# MCU.net
KiCad netlist of a schematic drawn in Altium Designer
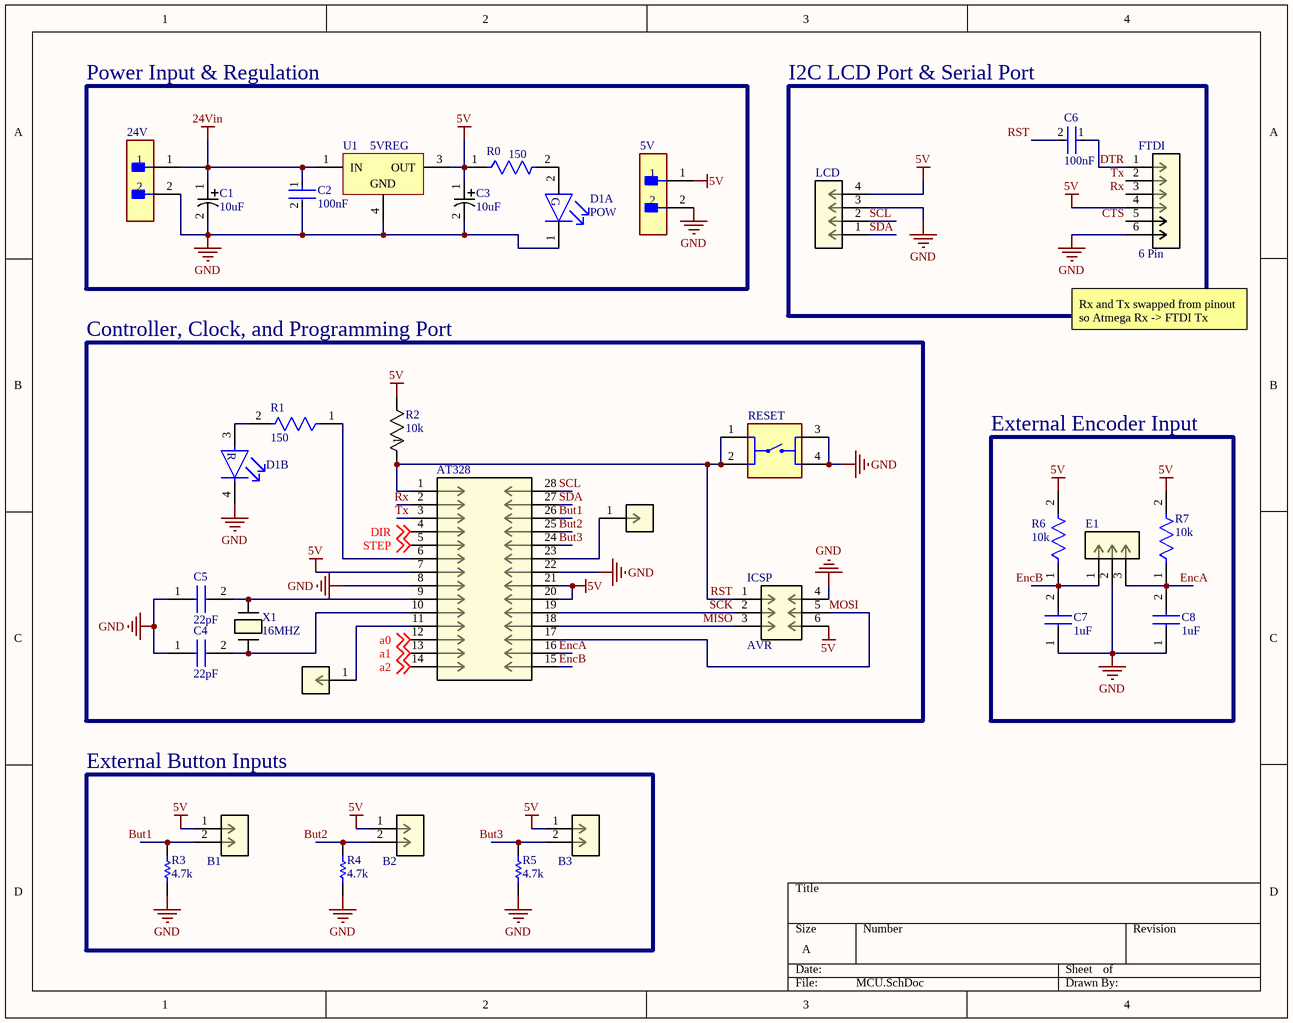
[diagram p0: MCU.SchDoc]

(export (version "E")
  (design (tool "Eeschema 10.0.6"))
  (components
    (comp (ref "5V")
      (value "~")
      (footprint "FP-TSW-102-07-L-S-MFG")
      (description "CONN HEADER VERT 2POS 2.54MM   TSW-102-07-L-S")
      (libsource (lib "Altium Content Vault") (part "3bc925449376181038e59eaffc5286c"))
    )
    (comp (ref "24V")
      (value "~")
      (footprint "FP-TSW-102-07-L-S-MFG")
      (description "CONN HEADER VERT 2POS 2.54MM   TSW-102-07-L-S")
      (libsource (lib "Altium Content Vault") (part "3bc925449376181038e59eaffc5286c"))
    )
    (comp (ref "AT328")
      (value "Atmega328")
      (footprint "PcbLib1:CONN28_1-2199298-9_TEC")
      (description "No Description Available   1-2199298-9")
      (fields
        (field (name "MANUFACTURER_PART_NUMBER") "1-2199298-9")
        (field (name "COPYRIGHT") "Copyright (C) 2022 Ultra Librarian. All rights reserved.")
      )
      (libsource (lib "Schlib1") (part "14x2_J"))
    )
    (comp (ref "B1")
      (value "Header")
      (footprint "PcbLib1:1x2StanHeader")
      (description "No Description Available")
      (fields
        (field (name "MANUFACTURER_PART_NUMBER") "5-826631-0")
        (field (name "COPYRIGHT") "Copyright (C) 2018 Accelerated Designs. All rights reserved")
      )
      (libsource (lib "Schlib1") (part "2x1_J"))
    )
    (comp (ref "B2")
      (value "Header")
      (footprint "PcbLib1:1x2StanHeader")
      (description "No Description Available")
      (fields
        (field (name "MANUFACTURER_PART_NUMBER") "5-826631-0")
        (field (name "COPYRIGHT") "Copyright (C) 2018 Accelerated Designs. All rights reserved")
      )
      (libsource (lib "Schlib1") (part "2x1_J"))
    )
    (comp (ref "B3")
      (value "Header")
      (footprint "PcbLib1:1x2StanHeader")
      (description "No Description Available")
      (fields
        (field (name "MANUFACTURER_PART_NUMBER") "5-826631-0")
        (field (name "COPYRIGHT") "Copyright (C) 2018 Accelerated Designs. All rights reserved")
      )
      (libsource (lib "Schlib1") (part "2x1_J"))
    )
    (comp (ref "C1")
      (value "10uF")
      (footprint "PcbLib1:CAP_EEE_C_PAN-M")
      (description "EEE-1VA100SR")
      (fields (field (name "COPYRIGHT") "Copyright (C) 2022 Ultra Librarian. All rights reserved."))
      (libsource (lib "Schlib1") (part "EEE-1VA100SR"))
    )
    (comp (ref "C2")
      (value "100nF")
      (footprint "FP-CL21-IPC_C")
      (description "CL21 Series 0805 100nF 50V ±10% Tolerance X7R Multilayer Ceramic Chip Capacitor CL21B104KBCNNNC")
      (fields (field (name "TOLERANCE") "10%") (field (name "VOLTAGE") "50V"))
      (libsource (lib "Altium Content Vault") (part "b4654b650e69147ec39a6b967a45e02"))
    )
    (comp (ref "C3")
      (value "10uF")
      (footprint "PcbLib1:CAP_EEE_C_PAN-M")
      (description "EEE-1VA100SR")
      (fields (field (name "COPYRIGHT") "Copyright (C) 2022 Ultra Librarian. All rights reserved."))
      (libsource (lib "Schlib1") (part "EEE-1VA100SR"))
    )
    (comp (ref "C4")
      (value "22pF")
      (footprint "PcbLib1:C0805")
      (description "Capacitor C0805C220J4GACTU")
      (fields
        (field (name "MOUSER2 PART NUMBER") "80-C0805C220J4GACTU")
        (field (name "MANUFACTURER_PART_NUMBER") "C0805C220J4GACTU")
      )
      (libsource (lib "Schlib1") (part "C0805C220J4GACTU"))
    )
    (comp (ref "C5")
      (value "22pF")
      (footprint "PcbLib1:C0805")
      (description "Capacitor C0805C220J4GACTU")
      (fields
        (field (name "MOUSER2 PART NUMBER") "80-C0805C220J4GACTU")
        (field (name "MANUFACTURER_PART_NUMBER") "C0805C220J4GACTU")
      )
      (libsource (lib "Schlib1") (part "C0805C220J4GACTU"))
    )
    (comp (ref "C6")
      (value "100nF")
      (footprint "FP-CL21-IPC_C")
      (description "CL21 Series 0805 100nF 50V ±10% Tolerance X7R Multilayer Ceramic Chip Capacitor CL21B104KBCNNNC")
      (fields (field (name "TOLERANCE") "10%") (field (name "VOLTAGE") "50V"))
      (libsource (lib "Altium Content Vault") (part "b4654b650e69147ec39a6b967a45e02"))
    )
    (comp (ref "C7")
      (value "1uF")
      (footprint "PcbLib1:CAPC2012X135N")
      (description "Capacitor CL21B105KAFNNNE")
      (fields
        (field (name "MANUFACTURER_PART_NUMBER") "CL21B105KAFNNNE")
        (field (name "MOUSER PART NUMBER") "187-CL21B105KAFNNNE")
      )
      (libsource (lib "Schlib1") (part "CL21B105KAFNNNE"))
    )
    (comp (ref "C8")
      (value "1uF")
      (footprint "PcbLib1:CAPC2012X135N")
      (description "Capacitor CL21B105KAFNNNE")
      (fields
        (field (name "MANUFACTURER_PART_NUMBER") "CL21B105KAFNNNE")
        (field (name "MOUSER PART NUMBER") "187-CL21B105KAFNNNE")
      )
      (libsource (lib "Schlib1") (part "CL21B105KAFNNNE"))
    )
    (comp (ref "D1")
      (value "POW")
      (footprint "FP-LTST-C235KGKRKT-MFG")
      (description "LED GREEN/RED CLEAR CHIP SMD LTST-C235KGKRKT")
      (libsource (lib "Altium Content Vault") (part "5532c11a9016f0da2f6b1749dd462ab"))
    )
    (comp (ref "E1")
      (value "Encoder")
      (footprint "PcbLib1:1x3StanHeader")
      (description "No Description Available")
      (fields
        (field (name "MANUFACTURER_PART_NUMBER") "5-826631-0")
        (field (name "COPYRIGHT") "Copyright (C) 2018 Accelerated Designs. All rights reserved")
      )
      (libsource (lib "Schlib1") (part "3x1_J"))
    )
    (comp (ref "FTDI")
      (value "6 Pin")
      (footprint "PcbLib1:USB FTDI 1x6")
      (description "No Description Available")
      (fields
        (field (name "MANUFACTURER_PART_NUMBER") "5-826631-0")
        (field (name "COPYRIGHT") "Copyright (C) 2018 Accelerated Designs. All rights reserved")
      )
      (libsource (lib "Schlib1") (part "FTDI USB"))
    )
    (comp (ref "ICSP")
      (value "AVR")
      (footprint "PcbLib1:2x3StanHeader")
      (description "No Description Available")
      (fields
        (field (name "MANUFACTURER_PART_NUMBER") "5-826631-0")
        (field (name "COPYRIGHT") "Copyright (C) 2018 Accelerated Designs. All rights reserved")
      )
      (libsource (lib "Schlib1") (part "2x3_J"))
    )
    (comp (ref "JB")
      (value "Header")
      (footprint "PcbLib1:1x1StanHeader")
      (description "No Description Available")
      (fields
        (field (name "MANUFACTURER_PART_NUMBER") "5-826631-0")
        (field (name "COPYRIGHT") "Copyright (C) 2018 Accelerated Designs. All rights reserved")
      )
      (libsource (lib "Schlib1") (part "1x1_J"))
    )
    (comp (ref "JC")
      (value "Header")
      (footprint "PcbLib1:1x1StanHeader")
      (description "No Description Available")
      (fields
        (field (name "MANUFACTURER_PART_NUMBER") "5-826631-0")
        (field (name "COPYRIGHT") "Copyright (C) 2018 Accelerated Designs. All rights reserved")
      )
      (libsource (lib "") (part "1x1_J_1"))
    )
    (comp (ref "LCD")
      (value "LCD")
      (footprint "PcbLib1:1x4StanHeader")
      (description "No Description Available")
      (fields
        (field (name "MANUFACTURER_PART_NUMBER") "5-826631-0")
        (field (name "COPYRIGHT") "Copyright (C) 2018 Accelerated Designs. All rights reserved")
      )
      (libsource (lib "Schlib1") (part "4x1_J"))
    )
    (comp (ref "R0")
      (value "150")
      (footprint "FP-ERJ6GE-MFG")
      (description "RES SMD 150 OHM 5% 1/8W 0805 ERJ-6GEYJ151V")
      (fields (field (name "TOLERANCE") "5%") (field (name "MANUFACTURER PART NUMBER") "ERJ-6GEYJ151V"))
      (libsource (lib "Altium Content Vault") (part "1029c3af85768c4190bb7ad29bc67b5"))
    )
    (comp (ref "R1")
      (value "150")
      (footprint "FP-ERJ6GE-MFG")
      (description "RES SMD 150 OHM 5% 1/8W 0805 ERJ-6GEYJ151V")
      (fields (field (name "TOLERANCE") "5%") (field (name "MANUFACTURER PART NUMBER") "ERJ-6GEYJ151V"))
      (libsource (lib "Altium Content Vault") (part "1029c3af85768c4190bb7ad29bc67b5"))
    )
    (comp (ref "R2")
      (value "10k")
      (footprint "PcbLib1:RES_AC0805_YAG-M")
      (description "AC0805FR-070RL")
      (fields (field (name "COPYRIGHT") "Copyright (C) 2022 Ultra Librarian. All rights reserved."))
      (libsource (lib "Schlib1") (part "AC0805FR-070RL"))
    )
    (comp (ref "R3")
      (value "4.7k")
      (footprint "RESC2013X50X30LL20T20")
      (description "CRCW08054K70JNEB")
      (fields (field (name "MANUFACTURER") "Vishay Dale"))
      (libsource (lib "Altium Content Vault") (part "RES"))
    )
    (comp (ref "R4")
      (value "4.7k")
      (footprint "RESC2013X50X30LL20T20")
      (description "CRCW08054K70JNEB")
      (fields (field (name "MANUFACTURER") "Vishay Dale"))
      (libsource (lib "Altium Content Vault") (part "RES"))
    )
    (comp (ref "R5")
      (value "4.7k")
      (footprint "RESC2013X50X30LL20T20")
      (description "CRCW08054K70JNEB")
      (fields (field (name "MANUFACTURER") "Vishay Dale"))
      (libsource (lib "Altium Content Vault") (part "RES"))
    )
    (comp (ref "R6")
      (value "10k")
      (footprint "FP-MC01W0805-IPC_C")
      (description "Resistor, 10K, 0.1W, 1%, 0805, Reel MC01W0805110K")
      (fields (field (name "TOLERANCE") "1%"))
      (libsource (lib "Altium Content Vault") (part "1029c3af85768c4190bb7ad29bc67b5"))
    )
    (comp (ref "R7")
      (value "10k")
      (footprint "FP-MC01W0805-IPC_C")
      (description "Resistor, 10K, 0.1W, 1%, 0805, Reel MC01W0805110K")
      (fields (field (name "TOLERANCE") "1%"))
      (libsource (lib "Altium Content Vault") (part "1029c3af85768c4190bb7ad29bc67b5"))
    )
    (comp (ref "RESET")
      (value "Reset")
      (footprint "SW_1825910-6-4")
      (description "Switch Tactile OFF (ON) SPST Round Button PC Pins 0.05A 24VDC 100000Cycles 1.57N Thru-Hole Loose")
      (fields (field (name "MP") "1825910-6"))
      (libsource (lib "Panther Racing") (part "1825910-6"))
    )
    (comp (ref "U1")
      (value "5VREG")
      (footprint "TO-263_M")
      (description "Positive Voltage Regulator, 3-Pin D2PAK, Tape and Reel L7805CD2T-TR")
      (libsource (lib "Altium Content Vault") (part "PM-REG-L4940-SOT3"))
    )
    (comp (ref "X1")
      (value "16MHZ")
      (footprint "XTAL_ATS-49_CTS")
      (description "ATS-49/U-16.0000MHZ")
      (fields (field (name "COPYRIGHT") "Copyright (C) 2022 Ultra Librarian. All rights reserved."))
      (libsource (lib "Schlib1") (part "ATS-49/U-16.0000MHZ"))
    )
  )
  (nets
    (net (code "1") (name "/But1") (class "Default")
      (node (ref "AT328") (pin "26") (pinfunction "26_26") (pintype "passive"))
      (node (ref "B1") (pin "2") (pinfunction "2_2") (pintype "passive"))
      (node (ref "R3") (pin "2") (pinfunction "2_2") (pintype "passive"))
    )
    (net (code "2") (name "/But2") (class "Default")
      (node (ref "AT328") (pin "25") (pinfunction "25_25") (pintype "passive"))
      (node (ref "B2") (pin "2") (pinfunction "2_2") (pintype "passive"))
      (node (ref "R4") (pin "2") (pinfunction "2_2") (pintype "passive"))
    )
    (net (code "3") (name "/But3") (class "Default")
      (node (ref "AT328") (pin "24") (pinfunction "24_24") (pintype "passive"))
      (node (ref "B3") (pin "2") (pinfunction "2_2") (pintype "passive"))
      (node (ref "R5") (pin "2") (pinfunction "2_2") (pintype "passive"))
    )
    (net (code "4") (name "/CTS") (class "Default")
      (node (ref "FTDI") (pin "5") (pinfunction "5_5") (pintype "passive"))
    )
    (net (code "5") (name "/DTR") (class "Default")
      (node (ref "C6") (pin "1") (pinfunction "1_1") (pintype "passive"))
      (node (ref "FTDI") (pin "1") (pinfunction "1_1") (pintype "passive"))
    )
    (net (code "6") (name "/EncA") (class "Default")
      (node (ref "AT328") (pin "16") (pinfunction "16_16") (pintype "passive"))
      (node (ref "C8") (pin "2") (pinfunction "2_2") (pintype "passive"))
      (node (ref "E1") (pin "3") (pinfunction "3_3") (pintype "passive"))
      (node (ref "R7") (pin "1") (pinfunction "1_1") (pintype "passive"))
    )
    (net (code "7") (name "/EncB") (class "Default")
      (node (ref "AT328") (pin "15") (pinfunction "15_15") (pintype "passive"))
      (node (ref "C7") (pin "2") (pinfunction "2_2") (pintype "passive"))
      (node (ref "E1") (pin "1") (pinfunction "1_1") (pintype "passive"))
      (node (ref "R6") (pin "1") (pinfunction "1_1") (pintype "passive"))
    )
    (net (code "8") (name "/MISO") (class "Default")
      (node (ref "AT328") (pin "18") (pinfunction "18_18") (pintype "passive"))
      (node (ref "ICSP") (pin "3") (pinfunction "3_3") (pintype "passive"))
    )
    (net (code "9") (name "/MOSI") (class "Default")
      (node (ref "AT328") (pin "17") (pinfunction "17_17") (pintype "passive"))
      (node (ref "ICSP") (pin "5") (pinfunction "5_5") (pintype "passive"))
    )
    (net (code "10") (name "/RST") (class "Default")
      (node (ref "AT328") (pin "1") (pinfunction "1_1") (pintype "passive"))
      (node (ref "C6") (pin "2") (pinfunction "2_2") (pintype "passive"))
      (node (ref "ICSP") (pin "1") (pinfunction "1_1") (pintype "passive"))
      (node (ref "R2") (pin "1") (pinfunction "1_1") (pintype "passive"))
      (node (ref "RESET") (pin "1") (pinfunction "1_1") (pintype "passive"))
      (node (ref "RESET") (pin "2") (pinfunction "2_2") (pintype "passive"))
    )
    (net (code "11") (name "/Rx") (class "Default")
      (node (ref "AT328") (pin "2") (pinfunction "2_2") (pintype "passive"))
      (node (ref "FTDI") (pin "3") (pinfunction "3_3") (pintype "passive"))
    )
    (net (code "12") (name "/SCK") (class "Default")
      (node (ref "AT328") (pin "19") (pinfunction "19_19") (pintype "passive"))
      (node (ref "ICSP") (pin "2") (pinfunction "2_2") (pintype "passive"))
    )
    (net (code "13") (name "/SCL") (class "Default")
      (node (ref "AT328") (pin "28") (pinfunction "28_28") (pintype "passive"))
      (node (ref "LCD") (pin "2") (pinfunction "2_2") (pintype "passive"))
    )
    (net (code "14") (name "/SDA") (class "Default")
      (node (ref "AT328") (pin "27") (pinfunction "27_27") (pintype "passive"))
      (node (ref "LCD") (pin "1") (pinfunction "1_1") (pintype "passive"))
    )
    (net (code "15") (name "/Tx") (class "Default")
      (node (ref "AT328") (pin "3") (pinfunction "3_3") (pintype "passive"))
      (node (ref "FTDI") (pin "2") (pinfunction "2_2") (pintype "passive"))
    )
    (net (code "16") (name "5V") (class "Default")
      (node (ref "5V") (pin "1") (pinfunction "1_1") (pintype "passive"))
      (node (ref "AT328") (pin "20") (pinfunction "20_20") (pintype "passive"))
      (node (ref "AT328") (pin "21") (pinfunction "21_21") (pintype "passive"))
      (node (ref "AT328") (pin "7") (pinfunction "7_7") (pintype "passive"))
      (node (ref "B1") (pin "1") (pinfunction "1_1") (pintype "passive"))
      (node (ref "B2") (pin "1") (pinfunction "1_1") (pintype "passive"))
      (node (ref "B3") (pin "1") (pinfunction "1_1") (pintype "passive"))
      (node (ref "C3") (pin "1") (pinfunction "1_1") (pintype "passive"))
      (node (ref "FTDI") (pin "4") (pinfunction "4_4") (pintype "passive"))
      (node (ref "ICSP") (pin "6") (pinfunction "6_6") (pintype "passive"))
      (node (ref "LCD") (pin "4") (pinfunction "4_4") (pintype "passive"))
      (node (ref "R0") (pin "1") (pinfunction "1_1") (pintype "passive"))
      (node (ref "R2") (pin "2") (pinfunction "2_2") (pintype "passive"))
      (node (ref "R6") (pin "2") (pinfunction "2_2") (pintype "passive"))
      (node (ref "R7") (pin "2") (pinfunction "2_2") (pintype "passive"))
      (node (ref "U1") (pin "3") (pinfunction "OUT_3") (pintype "power_in"))
    )
    (net (code "17") (name "24Vin") (class "Default")
      (node (ref "24V") (pin "1") (pinfunction "1_1") (pintype "passive"))
      (node (ref "C1") (pin "1") (pinfunction "1_1") (pintype "passive"))
      (node (ref "C2") (pin "1") (pinfunction "1_1") (pintype "passive"))
      (node (ref "U1") (pin "1") (pinfunction "IN_1") (pintype "power_in"))
    )
    (net (code "18") (name "DIR") (class "Default")
      (node (ref "AT328") (pin "4") (pinfunction "4_4") (pintype "passive"))
    )
    (net (code "19") (name "GND") (class "Default")
      (node (ref "24V") (pin "2") (pinfunction "2_2") (pintype "passive"))
      (node (ref "5V") (pin "2") (pinfunction "2_2") (pintype "passive"))
      (node (ref "AT328") (pin "22") (pinfunction "22_22") (pintype "passive"))
      (node (ref "AT328") (pin "8") (pinfunction "8_8") (pintype "passive"))
      (node (ref "C1") (pin "2") (pinfunction "2_2") (pintype "passive"))
      (node (ref "C2") (pin "2") (pinfunction "2_2") (pintype "passive"))
      (node (ref "C3") (pin "2") (pinfunction "2_2") (pintype "passive"))
      (node (ref "C4") (pin "1") (pinfunction "1_1") (pintype "passive"))
      (node (ref "C5") (pin "1") (pinfunction "1_1") (pintype "passive"))
      (node (ref "C7") (pin "1") (pinfunction "1_1") (pintype "passive"))
      (node (ref "C8") (pin "1") (pinfunction "1_1") (pintype "passive"))
      (node (ref "D1") (pin "1") (pinfunction "Green_C_1") (pintype "passive"))
      (node (ref "D1") (pin "4") (pinfunction "Red_C_4") (pintype "passive"))
      (node (ref "E1") (pin "2") (pinfunction "2_2") (pintype "passive"))
      (node (ref "FTDI") (pin "6") (pinfunction "6_6") (pintype "passive"))
      (node (ref "ICSP") (pin "4") (pinfunction "4_4") (pintype "passive"))
      (node (ref "LCD") (pin "3") (pinfunction "3_3") (pintype "passive"))
      (node (ref "R3") (pin "1") (pinfunction "1_1") (pintype "passive"))
      (node (ref "R4") (pin "1") (pinfunction "1_1") (pintype "passive"))
      (node (ref "R5") (pin "1") (pinfunction "1_1") (pintype "passive"))
      (node (ref "RESET") (pin "3") (pinfunction "3_3") (pintype "passive"))
      (node (ref "RESET") (pin "4") (pinfunction "4_4") (pintype "passive"))
      (node (ref "U1") (pin "4") (pinfunction "GND_4") (pintype "power_in"))
    )
    (net (code "20") (name "Net-(AT328-Pad6)") (class "Default")
      (node (ref "AT328") (pin "6") (pinfunction "6_6") (pintype "passive"))
      (node (ref "R1") (pin "1") (pinfunction "1_1") (pintype "passive"))
    )
    (net (code "21") (name "Net-(AT328-Pad9)") (class "Default")
      (node (ref "AT328") (pin "9") (pinfunction "9_9") (pintype "passive"))
      (node (ref "C5") (pin "2") (pinfunction "2_2") (pintype "passive"))
      (node (ref "X1") (pin "2") (pinfunction "2_2") (pintype "passive"))
    )
    (net (code "22") (name "Net-(AT328-Pad10)") (class "Default")
      (node (ref "AT328") (pin "10") (pinfunction "10_10") (pintype "passive"))
      (node (ref "C4") (pin "2") (pinfunction "2_2") (pintype "passive"))
      (node (ref "X1") (pin "1") (pinfunction "1_1") (pintype "passive"))
    )
    (net (code "23") (name "Net-(AT328-Pad11)") (class "Default")
      (node (ref "AT328") (pin "11") (pinfunction "11_11") (pintype "passive"))
      (node (ref "JB") (pin "1") (pinfunction "1_1") (pintype "passive"))
    )
    (net (code "24") (name "Net-(AT328-Pad23)") (class "Default")
      (node (ref "AT328") (pin "23") (pinfunction "23_23") (pintype "passive"))
      (node (ref "JC") (pin "1") (pinfunction "1_1") (pintype "passive"))
    )
    (net (code "25") (name "Net-(D1A-Green_A)") (class "Default")
      (node (ref "D1") (pin "2") (pinfunction "Green_A_2") (pintype "passive"))
      (node (ref "R0") (pin "2") (pinfunction "2_2") (pintype "passive"))
    )
    (net (code "26") (name "Net-(D1B-Red_A)") (class "Default")
      (node (ref "D1") (pin "3") (pinfunction "Red_A_3") (pintype "passive"))
      (node (ref "R1") (pin "2") (pinfunction "2_2") (pintype "passive"))
    )
    (net (code "27") (name "STEP") (class "Default")
      (node (ref "AT328") (pin "5") (pinfunction "5_5") (pintype "passive"))
    )
    (net (code "28") (name "a0") (class "Default")
      (node (ref "AT328") (pin "12") (pinfunction "12_12") (pintype "passive"))
    )
    (net (code "29") (name "a1") (class "Default")
      (node (ref "AT328") (pin "13") (pinfunction "13_13") (pintype "passive"))
    )
    (net (code "30") (name "a2") (class "Default")
      (node (ref "AT328") (pin "14") (pinfunction "14_14") (pintype "passive"))
    )
  )
)
